# sheet1.net
KiCad netlist of a schematic drawn in Altium Designer
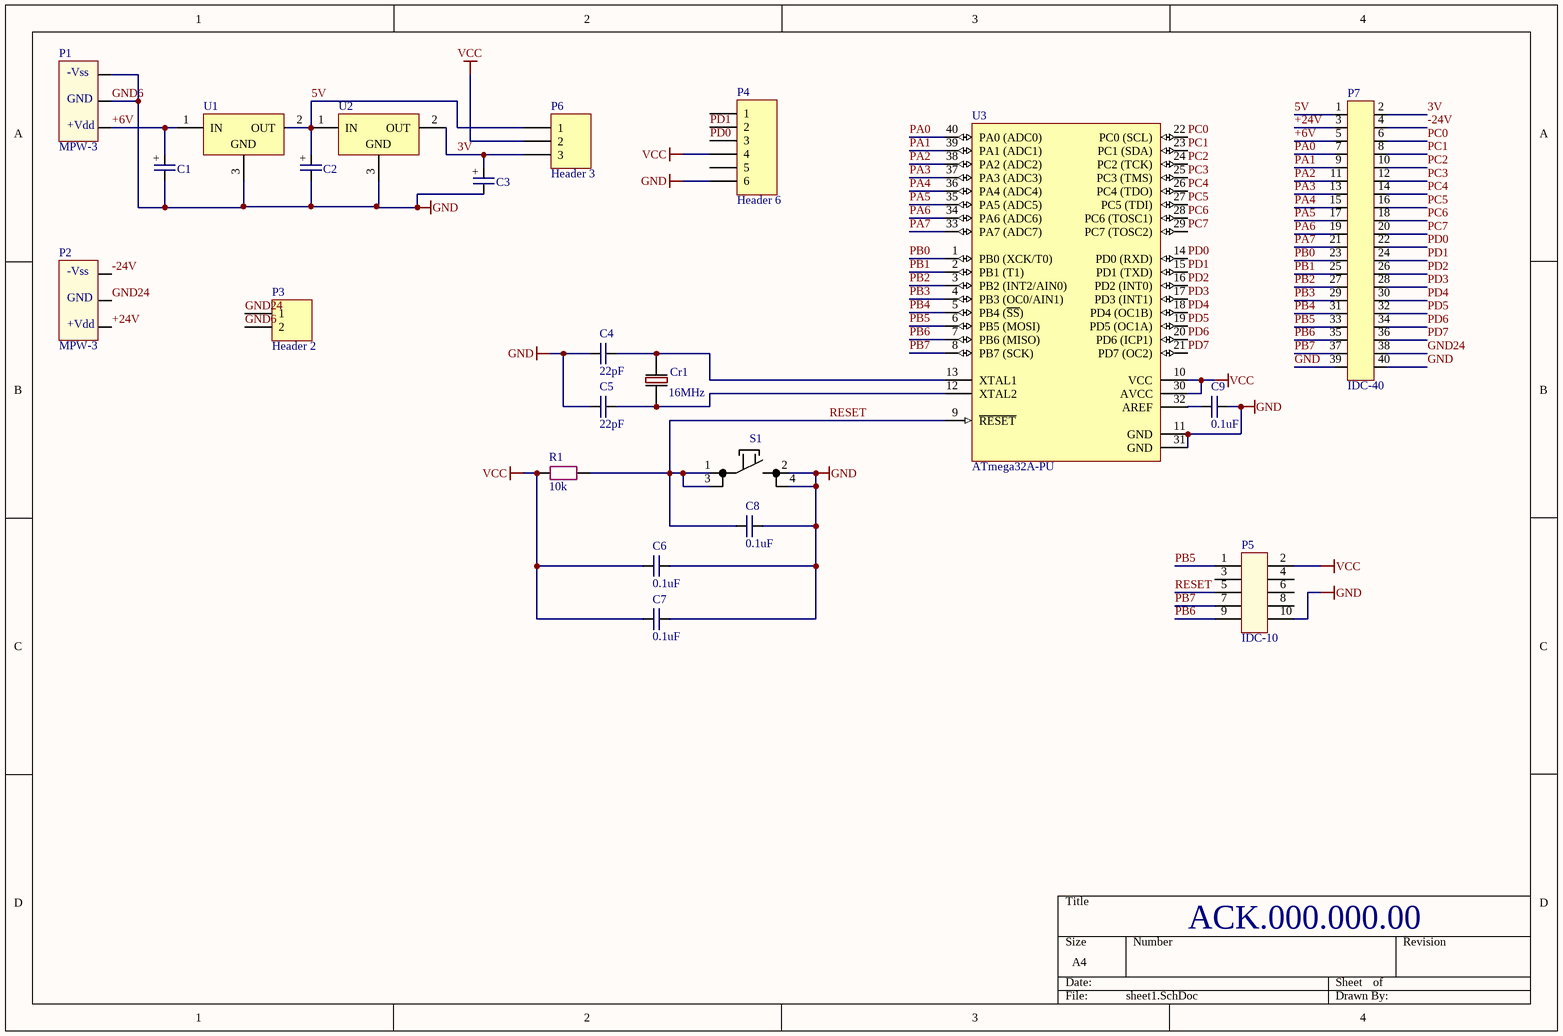
[diagram p0: sheet1.SchDoc]

(export (version "E")
  (design (tool "Eeschema 10.0.6"))
  (components
    (comp (ref "C1")
      (value "~")
      (footprint "RCU:C_TECAP_A")
      (libsource (lib "RCU") (part "capacitor_TECAP_SMD_A"))
    )
    (comp (ref "C2")
      (value "~")
      (footprint "RCU:C_TECAP_A")
      (libsource (lib "RCU") (part "capacitor_TECAP_SMD_A"))
    )
    (comp (ref "C3")
      (value "~")
      (footprint "RCU:C_TECAP_A")
      (libsource (lib "RCU") (part "capacitor_TECAP_SMD_A"))
    )
    (comp (ref "C4") (value "22pF") (footprint "RCU:C_0805") (libsource (lib "RCU") (part "capacitor 0805")))
    (comp (ref "C5") (value "22pF") (footprint "RCU:C_0805") (libsource (lib "RCU") (part "capacitor 0805")))
    (comp (ref "C6") (value "0.1uF") (footprint "RCU:C_0805") (libsource (lib "RCU") (part "capacitor 0805")))
    (comp (ref "C7") (value "0.1uF") (footprint "RCU:C_0805") (libsource (lib "RCU") (part "capacitor 0805")))
    (comp (ref "C8") (value "0.1uF") (footprint "RCU:C_0805") (libsource (lib "RCU") (part "capacitor 0805")))
    (comp (ref "C9") (value "0.1uF") (footprint "RCU:C_0805") (libsource (lib "RCU") (part "capacitor 0805")))
    (comp (ref "Cr1") (value "16MHz") (footprint "quarts_2.54") (libsource (lib "RCU") (part "quarts_2.54")))
    (comp (ref "P1") (value "MPW-3") (footprint "MPW-3") (libsource (lib "RCU") (part "MPW-3")))
    (comp (ref "P2") (value "MPW-3") (footprint "MPW-3") (libsource (lib "RCU") (part "MPW-3")))
    (comp (ref "P3")
      (value "Header 2")
      (footprint "HDR1X2")
      (description "Header, 2-Pin")
      (fields (field (name "PUBLISHER") "Altium Limited"))
      (libsource (lib "Miscellaneous Connectors") (part "Header 2"))
    )
    (comp (ref "P4")
      (value "Header 6")
      (footprint "HDR1X6")
      (description "Header, 6-Pin")
      (fields (field (name "PUBLISHER") "Altium Limited"))
      (libsource (lib "Miscellaneous Connectors") (part "Header 6"))
    )
    (comp (ref "P5")
      (value "IDC-10")
      (footprint "IDC-10")
      (description "разъем 4130")
      (libsource (lib "RCU") (part "IDC-10"))
    )
    (comp (ref "P6")
      (value "Header 3")
      (footprint "HDR1X3")
      (description "Header, 3-Pin")
      (fields (field (name "PUBLISHER") "Altium Limited"))
      (libsource (lib "Miscellaneous Connectors") (part "Header 3"))
    )
    (comp (ref "P7")
      (value "IDC-40")
      (footprint "IDC-40")
      (description "разъем 2529")
      (libsource (lib "RCU") (part "IDC-40"))
    )
    (comp (ref "R1") (value "10k") (footprint "RCU:R_0805") (libsource (lib "RCU") (part "resistor 0805")))
    (comp (ref "S1")
      (value "button 4 pin")
      (footprint "button 4 pin")
      (libsource (lib "RCU") (part "button 4 pin2"))
    )
    (comp (ref "U1")
      (value "~")
      (footprint "TO220ABN")
      (description "Precision 1A Regulator")
      (fields (field (name "PUBLISHER") "Altium Limited"))
      (libsource (lib "ST Power Mgt Voltage Regulator") (part "L7805ABV"))
    )
    (comp (ref "U2")
      (value "~")
      (footprint "TO220ABN")
      (description "Precision 1A Regulator")
      (fields (field (name "PUBLISHER") "Altium Limited"))
      (libsource (lib "ST Power Mgt Voltage Regulator") (part "L7805ABV"))
    )
    (comp (ref "U3")
      (value "ATmega32A-PU")
      (footprint "40P6")
      (fields (field (name "PUBLISHER") "Altium Limited"))
      (libsource (lib "Atmel Microcontroller 8-Bit megaAVR") (part "ATmega32A-PU"))
    )
  )
  (nets
    (net (code "1") (name "/+6V") (class "Default")
      (node (ref "C1") (pin "+") (pinfunction "+_+") (pintype "passive"))
      (node (ref "P1") (pin "3") (pinfunction "3_3") (pintype "passive"))
      (node (ref "P7") (pin "5") (pinfunction "5_5") (pintype "passive"))
      (node (ref "U1") (pin "1") (pinfunction "IN_1") (pintype "power_in"))
    )
    (net (code "2") (name "/+24V") (class "Default")
      (node (ref "P2") (pin "3") (pinfunction "3_3") (pintype "passive"))
      (node (ref "P7") (pin "3") (pinfunction "3_3") (pintype "passive"))
    )
    (net (code "3") (name "/-24V") (class "Default")
      (node (ref "P2") (pin "1") (pinfunction "1_1") (pintype "passive"))
      (node (ref "P7") (pin "4") (pinfunction "4_4") (pintype "passive"))
    )
    (net (code "4") (name "/3V") (class "Default")
      (node (ref "C3") (pin "+") (pinfunction "+_+") (pintype "passive"))
      (node (ref "P6") (pin "3") (pinfunction "3_3") (pintype "passive"))
      (node (ref "P7") (pin "2") (pinfunction "2_2") (pintype "passive"))
      (node (ref "U2") (pin "2") (pinfunction "OUT_2") (pintype "power_in"))
    )
    (net (code "5") (name "/5V") (class "Default")
      (node (ref "C2") (pin "+") (pinfunction "+_+") (pintype "passive"))
      (node (ref "P6") (pin "1") (pinfunction "1_1") (pintype "passive"))
      (node (ref "P7") (pin "1") (pinfunction "0_1") (pintype "passive"))
      (node (ref "U1") (pin "2") (pinfunction "OUT_2") (pintype "power_in"))
      (node (ref "U2") (pin "1") (pinfunction "IN_1") (pintype "power_in"))
    )
    (net (code "6") (name "/GND24") (class "Default")
      (node (ref "P2") (pin "2") (pinfunction "2_2") (pintype "passive"))
      (node (ref "P3") (pin "1") (pinfunction "1_1") (pintype "passive"))
      (node (ref "P7") (pin "38") (pinfunction "38_38") (pintype "passive"))
    )
    (net (code "7") (name "/PA0") (class "Default")
      (node (ref "P7") (pin "7") (pinfunction "7_7") (pintype "passive"))
      (node (ref "U3") (pin "40") (pinfunction "PA0_(ADC0)_40") (pintype "bidirectional"))
    )
    (net (code "8") (name "/PA1") (class "Default")
      (node (ref "P7") (pin "9") (pinfunction "9_9") (pintype "passive"))
      (node (ref "U3") (pin "39") (pinfunction "PA1_(ADC1)_39") (pintype "bidirectional"))
    )
    (net (code "9") (name "/PA2") (class "Default")
      (node (ref "P7") (pin "11") (pinfunction "11_11") (pintype "passive"))
      (node (ref "U3") (pin "38") (pinfunction "PA2_(ADC2)_38") (pintype "bidirectional"))
    )
    (net (code "10") (name "/PA3") (class "Default")
      (node (ref "P7") (pin "13") (pinfunction "13_13") (pintype "passive"))
      (node (ref "U3") (pin "37") (pinfunction "PA3_(ADC3)_37") (pintype "bidirectional"))
    )
    (net (code "11") (name "/PA4") (class "Default")
      (node (ref "P7") (pin "15") (pinfunction "15_15") (pintype "passive"))
      (node (ref "U3") (pin "36") (pinfunction "PA4_(ADC4)_36") (pintype "bidirectional"))
    )
    (net (code "12") (name "/PA5") (class "Default")
      (node (ref "P7") (pin "17") (pinfunction "17_17") (pintype "passive"))
      (node (ref "U3") (pin "35") (pinfunction "PA5_(ADC5)_35") (pintype "bidirectional"))
    )
    (net (code "13") (name "/PA6") (class "Default")
      (node (ref "P7") (pin "19") (pinfunction "19_19") (pintype "passive"))
      (node (ref "U3") (pin "34") (pinfunction "PA6_(ADC6)_34") (pintype "bidirectional"))
    )
    (net (code "14") (name "/PA7") (class "Default")
      (node (ref "P7") (pin "21") (pinfunction "21_21") (pintype "passive"))
      (node (ref "U3") (pin "33") (pinfunction "PA7_(ADC7)_33") (pintype "bidirectional"))
    )
    (net (code "15") (name "/PB0") (class "Default")
      (node (ref "P7") (pin "23") (pinfunction "23_23") (pintype "passive"))
      (node (ref "U3") (pin "1") (pinfunction "PB0_(XCK/T0)_1") (pintype "bidirectional"))
    )
    (net (code "16") (name "/PB1") (class "Default")
      (node (ref "P7") (pin "25") (pinfunction "25_25") (pintype "passive"))
      (node (ref "U3") (pin "2") (pinfunction "PB1_(T1)_2") (pintype "bidirectional"))
    )
    (net (code "17") (name "/PB2") (class "Default")
      (node (ref "P7") (pin "27") (pinfunction "27_27") (pintype "passive"))
      (node (ref "U3") (pin "3") (pinfunction "PB2_(INT2/AIN0)_3") (pintype "bidirectional"))
    )
    (net (code "18") (name "/PB3") (class "Default")
      (node (ref "P7") (pin "29") (pinfunction "29_29") (pintype "passive"))
      (node (ref "U3") (pin "4") (pinfunction "PB3_(OC0/AIN1)_4") (pintype "bidirectional"))
    )
    (net (code "19") (name "/PB4") (class "Default")
      (node (ref "P7") (pin "31") (pinfunction "31_31") (pintype "passive"))
      (node (ref "U3") (pin "5") (pinfunction "PB4_(~{SS})_5") (pintype "bidirectional"))
    )
    (net (code "20") (name "/PB5") (class "Default")
      (node (ref "P5") (pin "1") (pinfunction "1_1") (pintype "passive"))
      (node (ref "P7") (pin "33") (pinfunction "33_33") (pintype "passive"))
      (node (ref "U3") (pin "6") (pinfunction "PB5_(MOSI)_6") (pintype "bidirectional"))
    )
    (net (code "21") (name "/PB6") (class "Default")
      (node (ref "P5") (pin "9") (pinfunction "9_9") (pintype "passive"))
      (node (ref "P7") (pin "35") (pinfunction "35_35") (pintype "passive"))
      (node (ref "U3") (pin "7") (pinfunction "PB6_(MISO)_7") (pintype "bidirectional"))
    )
    (net (code "22") (name "/PB7") (class "Default")
      (node (ref "P5") (pin "7") (pinfunction "7_7") (pintype "passive"))
      (node (ref "P7") (pin "37") (pinfunction "37_37") (pintype "passive"))
      (node (ref "U3") (pin "8") (pinfunction "PB7_(SCK)_8") (pintype "bidirectional"))
    )
    (net (code "23") (name "/PC0") (class "Default")
      (node (ref "P7") (pin "6") (pinfunction "6_6") (pintype "passive"))
      (node (ref "U3") (pin "22") (pinfunction "PC0_(SCL)_22") (pintype "bidirectional"))
    )
    (net (code "24") (name "/PC1") (class "Default")
      (node (ref "P7") (pin "8") (pinfunction "8_8") (pintype "passive"))
      (node (ref "U3") (pin "23") (pinfunction "PC1_(SDA)_23") (pintype "bidirectional"))
    )
    (net (code "25") (name "/PC2") (class "Default")
      (node (ref "P7") (pin "10") (pinfunction "10_10") (pintype "passive"))
      (node (ref "U3") (pin "24") (pinfunction "PC2_(TCK)_24") (pintype "bidirectional"))
    )
    (net (code "26") (name "/PC3") (class "Default")
      (node (ref "P7") (pin "12") (pinfunction "12_12") (pintype "passive"))
      (node (ref "U3") (pin "25") (pinfunction "PC3_(TMS)_25") (pintype "bidirectional"))
    )
    (net (code "27") (name "/PC4") (class "Default")
      (node (ref "P7") (pin "14") (pinfunction "14_14") (pintype "passive"))
      (node (ref "U3") (pin "26") (pinfunction "PC4_(TDO)_26") (pintype "bidirectional"))
    )
    (net (code "28") (name "/PC5") (class "Default")
      (node (ref "P7") (pin "16") (pinfunction "16_16") (pintype "passive"))
      (node (ref "U3") (pin "27") (pinfunction "PC5_(TDI)_27") (pintype "bidirectional"))
    )
    (net (code "29") (name "/PC6") (class "Default")
      (node (ref "P7") (pin "18") (pinfunction "18_18") (pintype "passive"))
      (node (ref "U3") (pin "28") (pinfunction "PC6_(TOSC1)_28") (pintype "bidirectional"))
    )
    (net (code "30") (name "/PC7") (class "Default")
      (node (ref "P7") (pin "20") (pinfunction "20_20") (pintype "passive"))
      (node (ref "U3") (pin "29") (pinfunction "PC7_(TOSC2)_29") (pintype "bidirectional"))
    )
    (net (code "31") (name "/PD0") (class "Default")
      (node (ref "P4") (pin "3") (pinfunction "3_3") (pintype "passive"))
      (node (ref "P7") (pin "22") (pinfunction "22_22") (pintype "passive"))
      (node (ref "U3") (pin "14") (pinfunction "PD0_(RXD)_14") (pintype "bidirectional"))
    )
    (net (code "32") (name "/PD1") (class "Default")
      (node (ref "P4") (pin "2") (pinfunction "2_2") (pintype "passive"))
      (node (ref "P7") (pin "24") (pinfunction "24_24") (pintype "passive"))
      (node (ref "U3") (pin "15") (pinfunction "PD1_(TXD)_15") (pintype "bidirectional"))
    )
    (net (code "33") (name "/PD2") (class "Default")
      (node (ref "P7") (pin "26") (pinfunction "26_26") (pintype "passive"))
      (node (ref "U3") (pin "16") (pinfunction "PD2_(INT0)_16") (pintype "bidirectional"))
    )
    (net (code "34") (name "/PD3") (class "Default")
      (node (ref "P7") (pin "28") (pinfunction "28_28") (pintype "passive"))
      (node (ref "U3") (pin "17") (pinfunction "PD3_(INT1)_17") (pintype "bidirectional"))
    )
    (net (code "35") (name "/PD4") (class "Default")
      (node (ref "P7") (pin "30") (pinfunction "30_30") (pintype "passive"))
      (node (ref "U3") (pin "18") (pinfunction "PD4_(OC1B)_18") (pintype "bidirectional"))
    )
    (net (code "36") (name "/PD5") (class "Default")
      (node (ref "P7") (pin "32") (pinfunction "32_32") (pintype "passive"))
      (node (ref "U3") (pin "19") (pinfunction "PD5_(OC1A)_19") (pintype "bidirectional"))
    )
    (net (code "37") (name "/PD6") (class "Default")
      (node (ref "P7") (pin "34") (pinfunction "34_34") (pintype "passive"))
      (node (ref "U3") (pin "20") (pinfunction "PD6_(ICP1)_20") (pintype "bidirectional"))
    )
    (net (code "38") (name "/PD7") (class "Default")
      (node (ref "P7") (pin "36") (pinfunction "36_36") (pintype "passive"))
      (node (ref "U3") (pin "21") (pinfunction "PD7_(OC2)_21") (pintype "bidirectional"))
    )
    (net (code "39") (name "/RESET") (class "Default")
      (node (ref "C8") (pin "1") (pinfunction "1_1") (pintype "passive"))
      (node (ref "P5") (pin "5") (pinfunction "5_5") (pintype "passive"))
      (node (ref "R1") (pin "2") (pinfunction "2_2") (pintype "passive"))
      (node (ref "S1") (pin "1") (pinfunction "5_1") (pintype "passive"))
      (node (ref "S1") (pin "3") (pinfunction "3_3") (pintype "passive"))
      (node (ref "U3") (pin "9") (pinfunction "~{RESET}_9") (pintype "input"))
    )
    (net (code "40") (name "GND") (class "Default")
      (node (ref "C1") (pin "2") (pinfunction "2_2") (pintype "passive"))
      (node (ref "C2") (pin "2") (pinfunction "2_2") (pintype "passive"))
      (node (ref "C3") (pin "2") (pinfunction "2_2") (pintype "passive"))
      (node (ref "C4") (pin "1") (pinfunction "1_1") (pintype "passive"))
      (node (ref "C5") (pin "1") (pinfunction "1_1") (pintype "passive"))
      (node (ref "C6") (pin "2") (pinfunction "2_2") (pintype "passive"))
      (node (ref "C7") (pin "2") (pinfunction "2_2") (pintype "passive"))
      (node (ref "C8") (pin "2") (pinfunction "2_2") (pintype "passive"))
      (node (ref "C9") (pin "2") (pinfunction "2_2") (pintype "passive"))
      (node (ref "P1") (pin "1") (pinfunction "1_1") (pintype "passive"))
      (node (ref "P1") (pin "2") (pinfunction "2_2") (pintype "passive"))
      (node (ref "P3") (pin "2") (pinfunction "2_2") (pintype "passive"))
      (node (ref "P4") (pin "6") (pinfunction "6_6") (pintype "passive"))
      (node (ref "P5") (pin "10") (pinfunction "10_10") (pintype "passive"))
      (node (ref "P7") (pin "39") (pinfunction "39_39") (pintype "passive"))
      (node (ref "P7") (pin "40") (pinfunction "40_40") (pintype "passive"))
      (node (ref "S1") (pin "2") (pinfunction "2_2") (pintype "passive"))
      (node (ref "S1") (pin "4") (pinfunction "4_4") (pintype "passive"))
      (node (ref "U1") (pin "3") (pinfunction "GND_3") (pintype "power_in"))
      (node (ref "U2") (pin "3") (pinfunction "GND_3") (pintype "power_in"))
      (node (ref "U3") (pin "11") (pinfunction "GND_11") (pintype "power_in"))
      (node (ref "U3") (pin "31") (pinfunction "GND_31") (pintype "power_in"))
    )
    (net (code "41") (name "Net-(U3-AREF)") (class "Default")
      (node (ref "C9") (pin "1") (pinfunction "1_1") (pintype "passive"))
      (node (ref "U3") (pin "32") (pinfunction "AREF_32") (pintype "power_in"))
    )
    (net (code "42") (name "Net-(U3-XTAL1)") (class "Default")
      (node (ref "C4") (pin "2") (pinfunction "2_2") (pintype "passive"))
      (node (ref "Cr1") (pin "2") (pinfunction "2_2") (pintype "passive"))
      (node (ref "U3") (pin "13") (pinfunction "XTAL1_13") (pintype "passive"))
    )
    (net (code "43") (name "Net-(U3-XTAL2)") (class "Default")
      (node (ref "C5") (pin "2") (pinfunction "2_2") (pintype "passive"))
      (node (ref "Cr1") (pin "1") (pinfunction "1_1") (pintype "passive"))
      (node (ref "U3") (pin "12") (pinfunction "XTAL2_12") (pintype "passive"))
    )
    (net (code "44") (name "VCC") (class "Default")
      (node (ref "C6") (pin "1") (pinfunction "1_1") (pintype "passive"))
      (node (ref "C7") (pin "1") (pinfunction "1_1") (pintype "passive"))
      (node (ref "P4") (pin "4") (pinfunction "4_4") (pintype "passive"))
      (node (ref "P5") (pin "2") (pinfunction "2_2") (pintype "passive"))
      (node (ref "P6") (pin "2") (pinfunction "2_2") (pintype "passive"))
      (node (ref "R1") (pin "1") (pinfunction "1_1") (pintype "passive"))
      (node (ref "U3") (pin "10") (pinfunction "VCC_10") (pintype "power_in"))
      (node (ref "U3") (pin "30") (pinfunction "AVCC_30") (pintype "power_in"))
    )
    (net (code "45") (name "unconnected-(P4-Pad1)") (class "Default")
      (node (ref "P4") (pin "1") (pinfunction "1_1") (pintype "passive"))
    )
    (net (code "46") (name "unconnected-(P4-Pad5)") (class "Default")
      (node (ref "P4") (pin "5") (pinfunction "5_5") (pintype "passive"))
    )
    (net (code "47") (name "unconnected-(P5-Pad3)") (class "Default")
      (node (ref "P5") (pin "3") (pinfunction "3_3") (pintype "passive"))
    )
    (net (code "48") (name "unconnected-(P5-Pad4)") (class "Default")
      (node (ref "P5") (pin "4") (pinfunction "4_4") (pintype "passive"))
    )
    (net (code "49") (name "unconnected-(P5-Pad6)") (class "Default")
      (node (ref "P5") (pin "6") (pinfunction "6_6") (pintype "passive"))
    )
    (net (code "50") (name "unconnected-(P5-Pad8)") (class "Default")
      (node (ref "P5") (pin "8") (pinfunction "8_8") (pintype "passive"))
    )
  )
)
